# EDCPSU.net
KiCad netlist of a schematic drawn in EAGLE
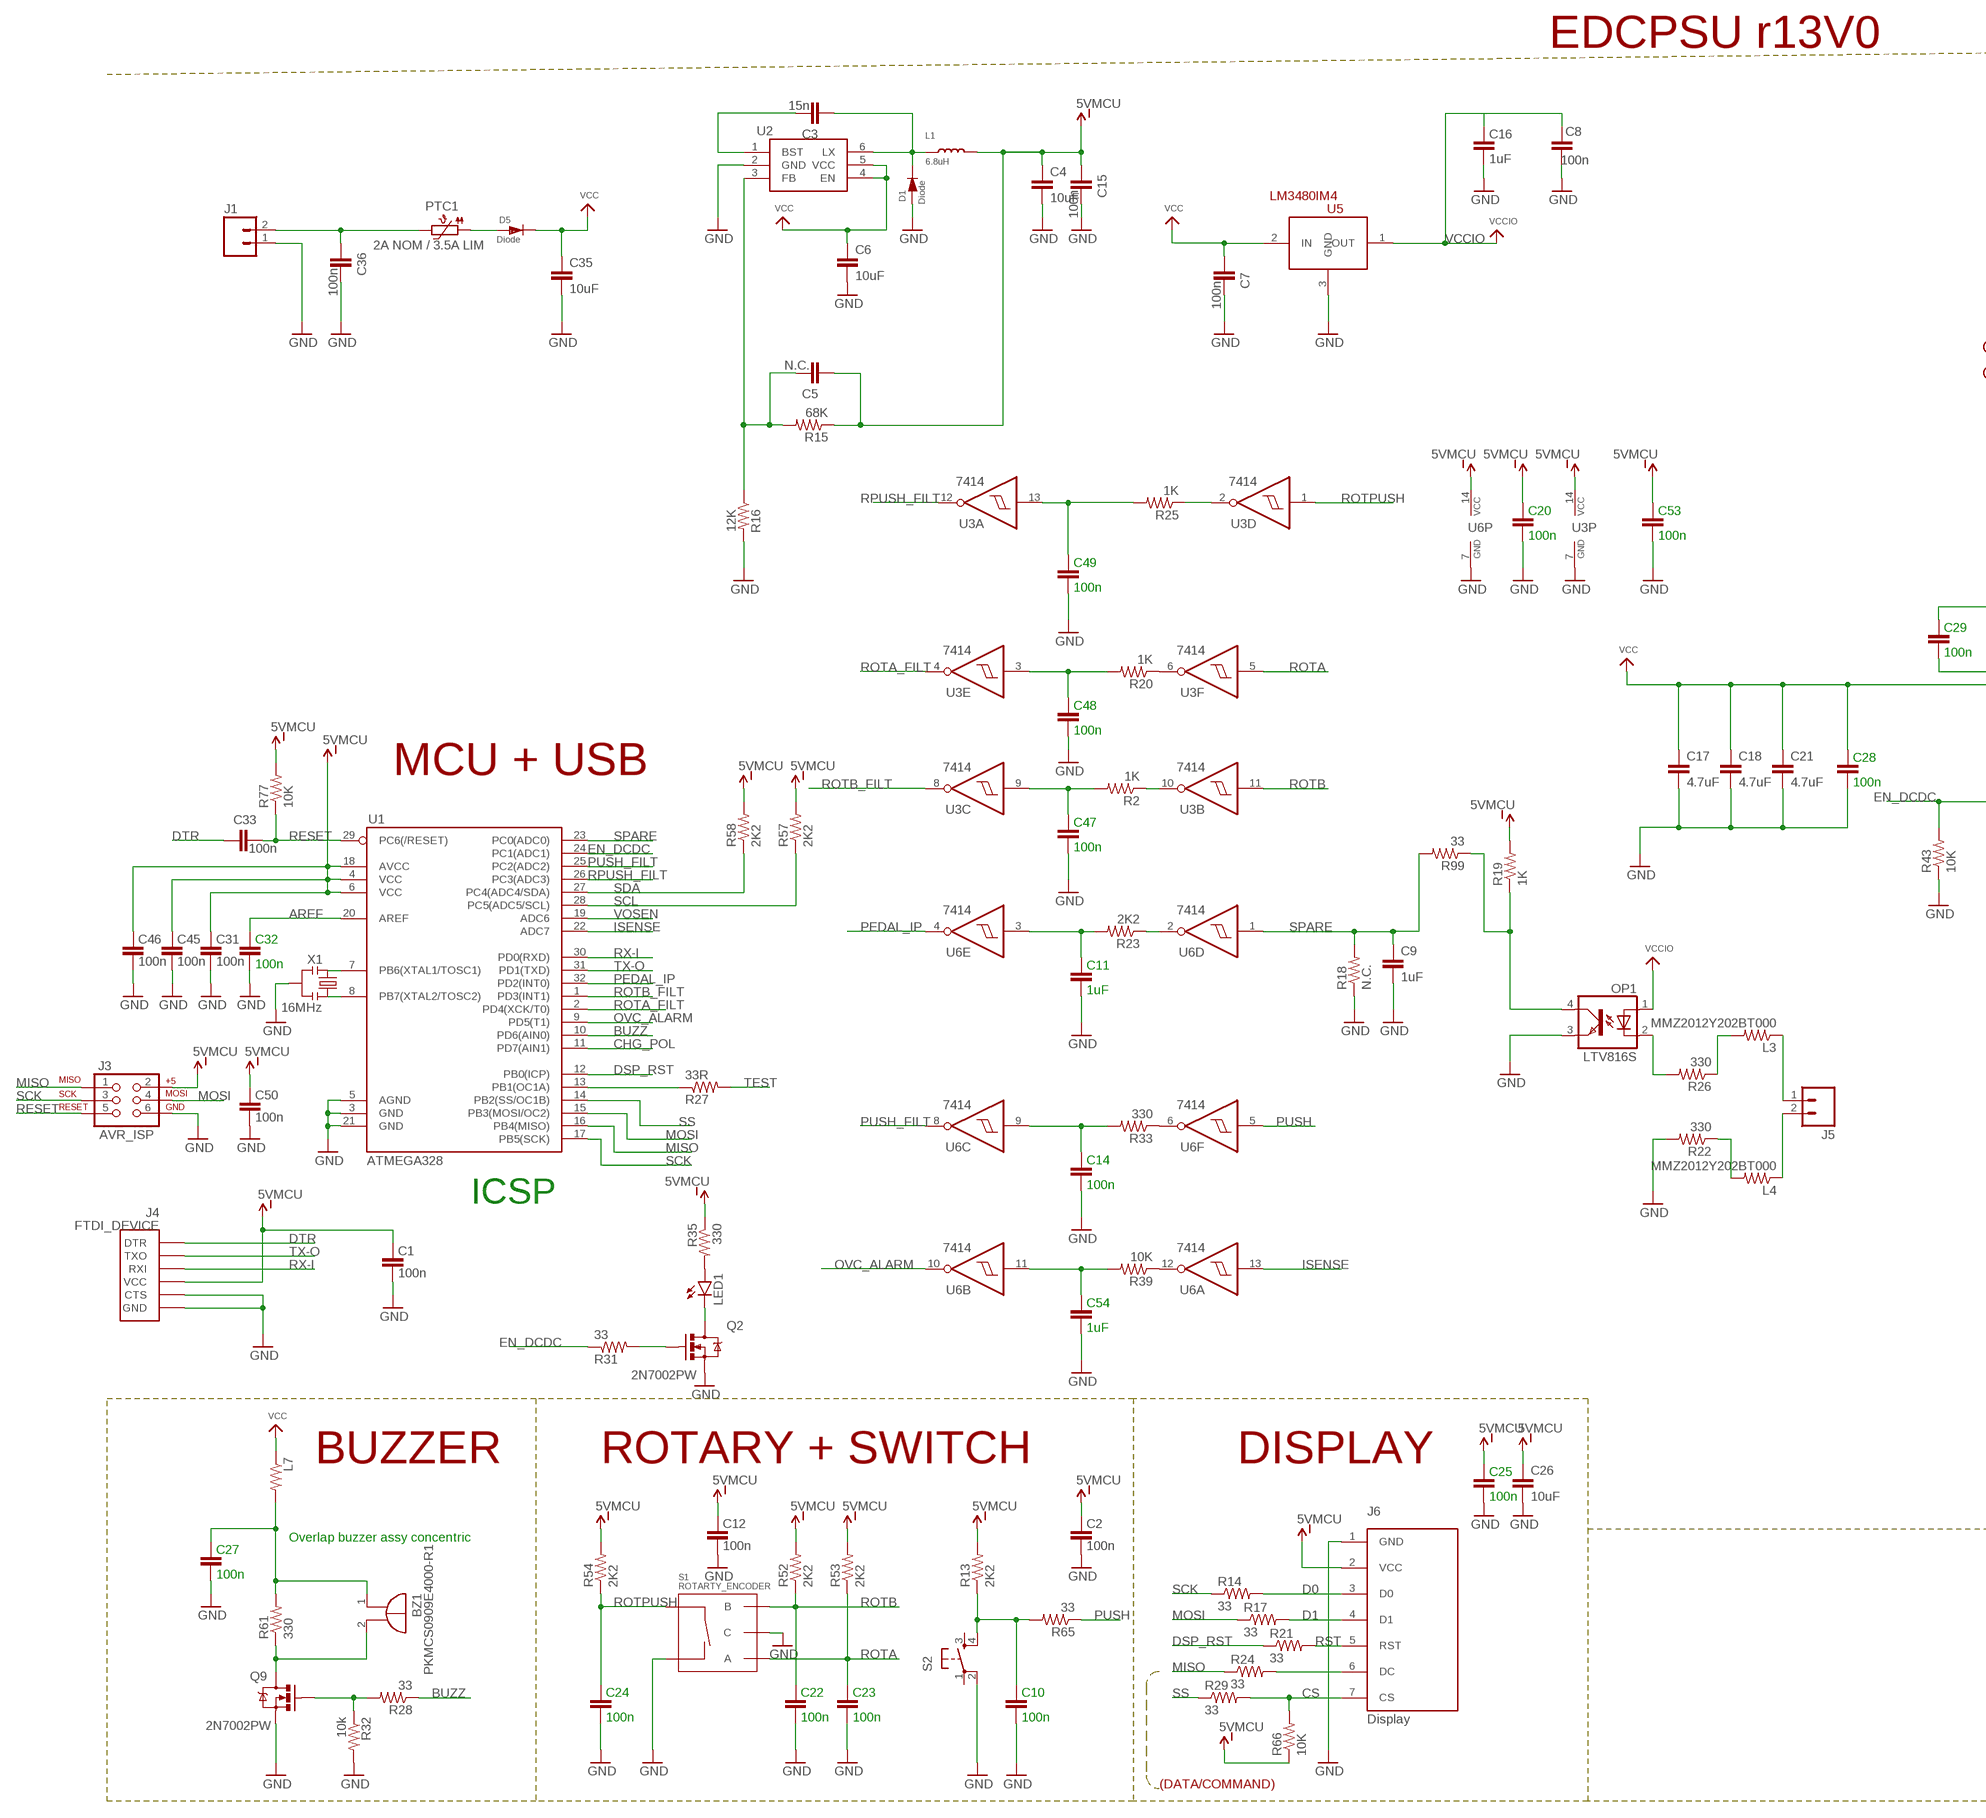
[diagram p0: schematic, sheet 1, part 1 of 2]
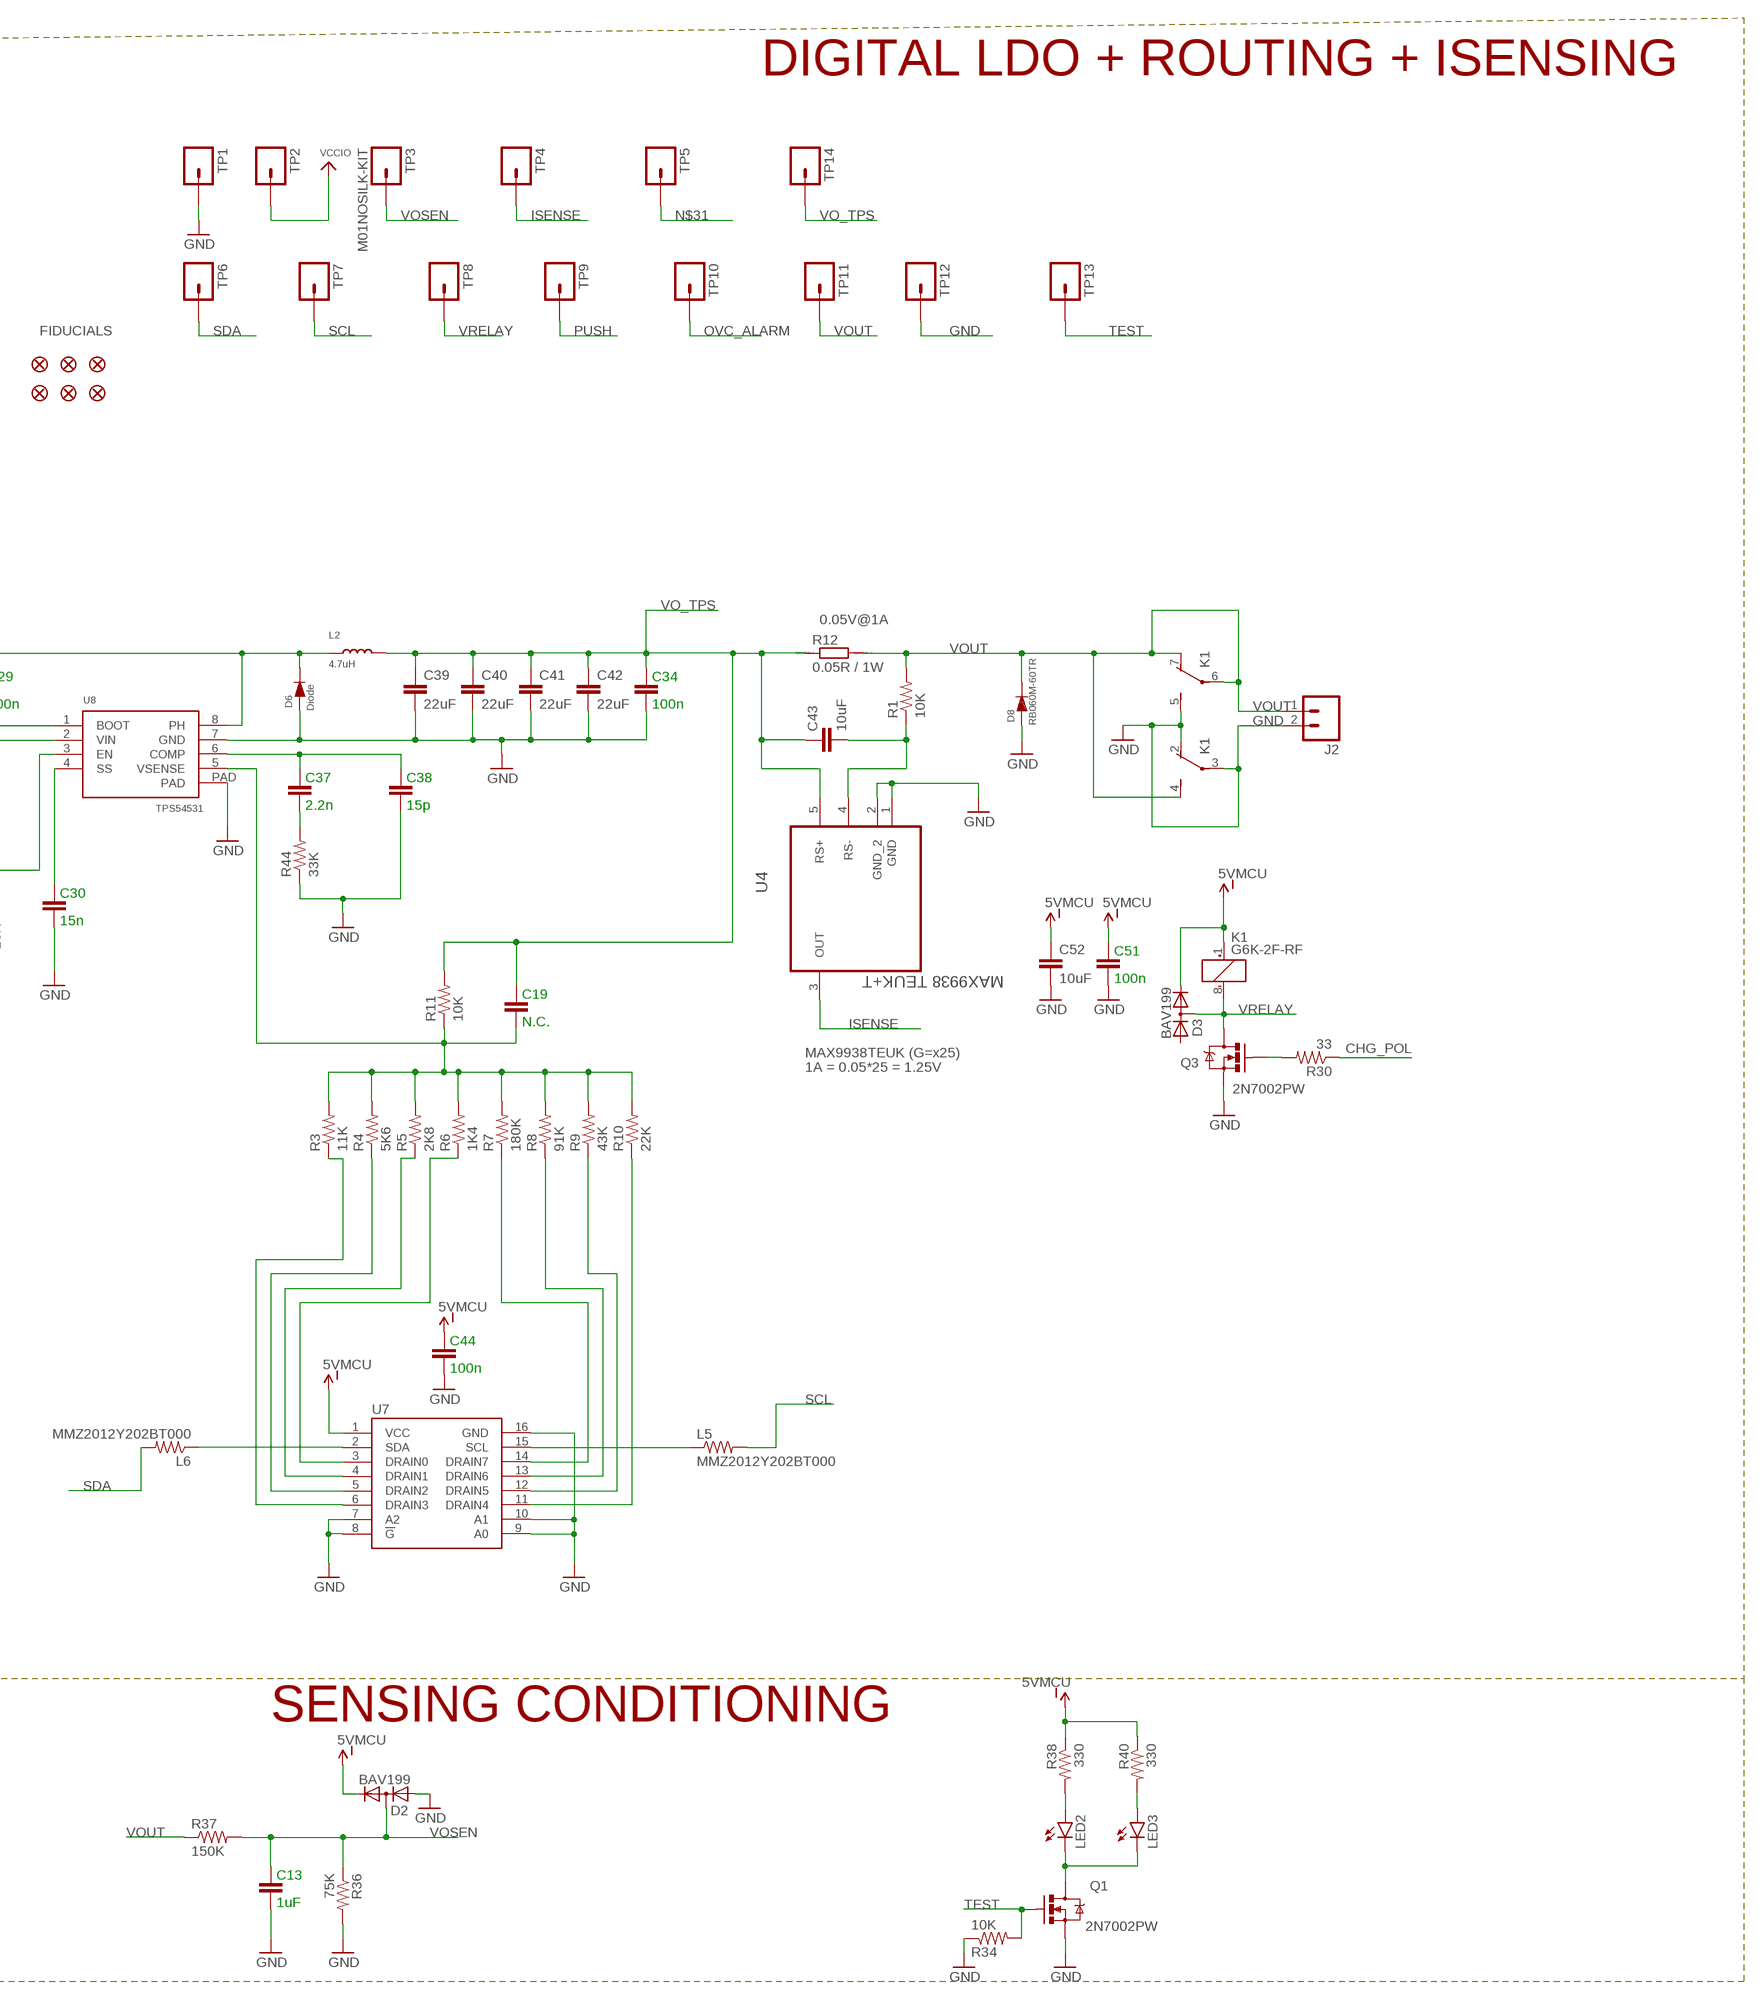
[diagram p1: schematic, sheet 1, part 2 of 2]

(export (version "E")
  (design (tool "Eeschema 10.0.6"))
  (components
    (comp (ref "BZ1")
      (value "PKMCS0909E4000-R1")
      (footprint "eagle-import:PKMCS0909")
      (libsource (lib "eagle-import") (part "PKMCS0909E4000-R1"))
    )
    (comp (ref "C1")
      (value "100n")
      (footprint "eagle-import:0805")
      (libsource (lib "eagle-import") (part "CAP0805"))
    )
    (comp (ref "C2")
      (value "100n")
      (footprint "eagle-import:0805")
      (libsource (lib "eagle-import") (part "CAP0805"))
    )
    (comp (ref "C3")
      (value "15n")
      (footprint "eagle-import:0805")
      (libsource (lib "eagle-import") (part "CAP0805"))
    )
    (comp (ref "C4")
      (value "10uF")
      (footprint "eagle-import:1206")
      (libsource (lib "eagle-import") (part "SparkFun-Passives_CAP1206"))
    )
    (comp (ref "C5")
      (value "N.C.")
      (footprint "eagle-import:0805")
      (libsource (lib "eagle-import") (part "CAP0805"))
    )
    (comp (ref "C6")
      (value "10uF")
      (footprint "eagle-import:1206")
      (libsource (lib "eagle-import") (part "SparkFun-Passives_CAP1206"))
    )
    (comp (ref "C7")
      (value "100n")
      (footprint "eagle-import:0805")
      (libsource (lib "eagle-import") (part "CAP0805"))
    )
    (comp (ref "C8")
      (value "100n")
      (footprint "eagle-import:0805")
      (libsource (lib "eagle-import") (part "CAP0805"))
    )
    (comp (ref "C9")
      (value "1uF")
      (footprint "eagle-import:1206")
      (libsource (lib "eagle-import") (part "SparkFun-Passives_CAP1206"))
    )
    (comp (ref "C10")
      (value "100n")
      (footprint "eagle-import:0805")
      (libsource (lib "eagle-import") (part "CAP0805"))
    )
    (comp (ref "C11")
      (value "1uF")
      (footprint "eagle-import:0805")
      (libsource (lib "eagle-import") (part "CAP0805"))
    )
    (comp (ref "C12")
      (value "100n")
      (footprint "eagle-import:0805")
      (libsource (lib "eagle-import") (part "CAP0805"))
    )
    (comp (ref "C13")
      (value "1uF")
      (footprint "eagle-import:0805")
      (libsource (lib "eagle-import") (part "CAP0805"))
    )
    (comp (ref "C14")
      (value "100n")
      (footprint "eagle-import:0805")
      (libsource (lib "eagle-import") (part "CAP0805"))
    )
    (comp (ref "C15")
      (value "100n")
      (footprint "eagle-import:0805")
      (libsource (lib "eagle-import") (part "CAP0805"))
    )
    (comp (ref "C16")
      (value "1uF")
      (footprint "eagle-import:0805")
      (libsource (lib "eagle-import") (part "CAP0805"))
    )
    (comp (ref "C17")
      (value "4.7uF")
      (footprint "eagle-import:1210")
      (libsource (lib "eagle-import") (part "SparkFun-Passives_CAP1210"))
    )
    (comp (ref "C18")
      (value "4.7uF")
      (footprint "eagle-import:1210")
      (libsource (lib "eagle-import") (part "SparkFun-Passives_CAP1210"))
    )
    (comp (ref "C19")
      (value "N.C.")
      (footprint "eagle-import:0805")
      (libsource (lib "eagle-import") (part "CAP0805"))
    )
    (comp (ref "C20")
      (value "100n")
      (footprint "eagle-import:0805")
      (libsource (lib "eagle-import") (part "CAP0805"))
    )
    (comp (ref "C21")
      (value "4.7uF")
      (footprint "eagle-import:1210")
      (libsource (lib "eagle-import") (part "SparkFun-Passives_CAP1210"))
    )
    (comp (ref "C22")
      (value "100n")
      (footprint "eagle-import:0805")
      (libsource (lib "eagle-import") (part "CAP0805"))
    )
    (comp (ref "C23")
      (value "100n")
      (footprint "eagle-import:0805")
      (libsource (lib "eagle-import") (part "CAP0805"))
    )
    (comp (ref "C24")
      (value "100n")
      (footprint "eagle-import:0805")
      (libsource (lib "eagle-import") (part "CAP0805"))
    )
    (comp (ref "C25")
      (value "100n")
      (footprint "eagle-import:0805")
      (libsource (lib "eagle-import") (part "CAP0805"))
    )
    (comp (ref "C26")
      (value "10uF")
      (footprint "eagle-import:1206")
      (libsource (lib "eagle-import") (part "SparkFun-Passives_CAP1206"))
    )
    (comp (ref "C27")
      (value "100n")
      (footprint "eagle-import:0805")
      (libsource (lib "eagle-import") (part "CAP0805"))
    )
    (comp (ref "C28")
      (value "100n")
      (footprint "eagle-import:0805")
      (libsource (lib "eagle-import") (part "CAP0805"))
    )
    (comp (ref "C29")
      (value "100n")
      (footprint "eagle-import:0805")
      (libsource (lib "eagle-import") (part "CAP0805"))
    )
    (comp (ref "C30")
      (value "15n")
      (footprint "eagle-import:0805")
      (libsource (lib "eagle-import") (part "CAP0805"))
    )
    (comp (ref "C31")
      (value "100n")
      (footprint "eagle-import:0805")
      (libsource (lib "eagle-import") (part "CAP0805"))
    )
    (comp (ref "C32")
      (value "100n")
      (footprint "eagle-import:0805")
      (libsource (lib "eagle-import") (part "CAP0805"))
    )
    (comp (ref "C33")
      (value "100n")
      (footprint "eagle-import:0805")
      (libsource (lib "eagle-import") (part "CAP0805"))
    )
    (comp (ref "C34")
      (value "100n")
      (footprint "eagle-import:0805")
      (libsource (lib "eagle-import") (part "CAP0805"))
    )
    (comp (ref "C35")
      (value "10uF")
      (footprint "eagle-import:1206")
      (libsource (lib "eagle-import") (part "SparkFun-Passives_CAP1206"))
    )
    (comp (ref "C36")
      (value "100n")
      (footprint "eagle-import:0805")
      (libsource (lib "eagle-import") (part "CAP0805"))
    )
    (comp (ref "C37")
      (value "2.2n")
      (footprint "eagle-import:0805")
      (libsource (lib "eagle-import") (part "CAP0805"))
    )
    (comp (ref "C38")
      (value "15p")
      (footprint "eagle-import:0805")
      (libsource (lib "eagle-import") (part "CAP0805"))
    )
    (comp (ref "C39")
      (value "22uF")
      (footprint "eagle-import:1210")
      (libsource (lib "eagle-import") (part "SparkFun-Passives_CAP1210"))
    )
    (comp (ref "C40")
      (value "22uF")
      (footprint "eagle-import:1210")
      (libsource (lib "eagle-import") (part "SparkFun-Passives_CAP1210"))
    )
    (comp (ref "C41")
      (value "22uF")
      (footprint "eagle-import:1210")
      (libsource (lib "eagle-import") (part "SparkFun-Passives_CAP1210"))
    )
    (comp (ref "C42")
      (value "22uF")
      (footprint "eagle-import:1210")
      (libsource (lib "eagle-import") (part "SparkFun-Passives_CAP1210"))
    )
    (comp (ref "C43")
      (value "10uF")
      (footprint "eagle-import:1206")
      (libsource (lib "eagle-import") (part "SparkFun-Passives_CAP1206"))
    )
    (comp (ref "C44")
      (value "100n")
      (footprint "eagle-import:0805")
      (libsource (lib "eagle-import") (part "CAP0805"))
    )
    (comp (ref "C45")
      (value "100n")
      (footprint "eagle-import:0805")
      (libsource (lib "eagle-import") (part "CAP0805"))
    )
    (comp (ref "C46")
      (value "100n")
      (footprint "eagle-import:0805")
      (libsource (lib "eagle-import") (part "CAP0805"))
    )
    (comp (ref "C47")
      (value "100n")
      (footprint "eagle-import:0805")
      (libsource (lib "eagle-import") (part "CAP0805"))
    )
    (comp (ref "C48")
      (value "100n")
      (footprint "eagle-import:0805")
      (libsource (lib "eagle-import") (part "CAP0805"))
    )
    (comp (ref "C49")
      (value "100n")
      (footprint "eagle-import:0805")
      (libsource (lib "eagle-import") (part "CAP0805"))
    )
    (comp (ref "C50")
      (value "100n")
      (footprint "eagle-import:0805")
      (libsource (lib "eagle-import") (part "CAP0805"))
    )
    (comp (ref "C51")
      (value "100n")
      (footprint "eagle-import:0805")
      (libsource (lib "eagle-import") (part "CAP0805"))
    )
    (comp (ref "C52")
      (value "10uF")
      (footprint "eagle-import:1206")
      (libsource (lib "eagle-import") (part "SparkFun-Passives_CAP1206"))
    )
    (comp (ref "C53")
      (value "100n")
      (footprint "eagle-import:0805")
      (libsource (lib "eagle-import") (part "CAP0805"))
    )
    (comp (ref "C54")
      (value "1uF")
      (footprint "eagle-import:0805")
      (libsource (lib "eagle-import") (part "CAP0805"))
    )
    (comp (ref "D1")
      (value "Diode")
      (footprint "eagle-import:SOD123")
      (libsource (lib "eagle-import") (part "DSOD123"))
    )
    (comp (ref "D2")
      (value "BAV199")
      (footprint "eagle-import:SOT23")
      (libsource (lib "eagle-import") (part "BAV199"))
    )
    (comp (ref "D3")
      (value "BAV199")
      (footprint "eagle-import:SOT23")
      (libsource (lib "eagle-import") (part "BAV199"))
    )
    (comp (ref "D5")
      (value "Diode")
      (footprint "eagle-import:DO-214AB")
      (libsource (lib "eagle-import") (part "DSMC"))
    )
    (comp (ref "D6")
      (value "Diode")
      (footprint "eagle-import:DO-214AB")
      (libsource (lib "eagle-import") (part "DSMC"))
    )
    (comp (ref "D8")
      (value "RB060M-60TR")
      (footprint "eagle-import:SMADIODE")
      (libsource (lib "eagle-import") (part "DSMA"))
    )
    (comp (ref "FID1")
      (value "FIDUCIAL1X2")
      (footprint "eagle-import:FIDUCIAL-1X2")
      (libsource (lib "eagle-import") (part "FIDUCIAL1X2"))
    )
    (comp (ref "FID2")
      (value "FIDUCIAL1X2")
      (footprint "eagle-import:FIDUCIAL-1X2")
      (libsource (lib "eagle-import") (part "FIDUCIAL1X2"))
    )
    (comp (ref "FID3")
      (value "FIDUCIAL1X2")
      (footprint "eagle-import:FIDUCIAL-1X2")
      (libsource (lib "eagle-import") (part "FIDUCIAL1X2"))
    )
    (comp (ref "FID4")
      (value "FIDUCIAL1X2")
      (footprint "eagle-import:FIDUCIAL-1X2")
      (libsource (lib "eagle-import") (part "FIDUCIAL1X2"))
    )
    (comp (ref "FID5")
      (value "FIDUCIAL1X2")
      (footprint "eagle-import:FIDUCIAL-1X2")
      (libsource (lib "eagle-import") (part "FIDUCIAL1X2"))
    )
    (comp (ref "FID6")
      (value "FIDUCIAL1X2")
      (footprint "eagle-import:FIDUCIAL-1X2")
      (libsource (lib "eagle-import") (part "FIDUCIAL1X2"))
    )
    (comp (ref "J1")
      (value "M02LOCK_LONGPADS")
      (footprint "eagle-import:1X02_LOCK_LONGPADS")
      (libsource (lib "eagle-import") (part "M02LOCK_LONGPADS"))
    )
    (comp (ref "J2")
      (value "M02LOCK_LONGPADS")
      (footprint "eagle-import:1X02_LOCK_LONGPADS")
      (libsource (lib "eagle-import") (part "M02LOCK_LONGPADS"))
    )
    (comp (ref "J3")
      (value "AVR_ISP")
      (footprint "eagle-import:2X3")
      (libsource (lib "eagle-import") (part "AVR_SPI_PRG_6PTH"))
    )
    (comp (ref "J4")
      (value "FTDI_DEVICE")
      (footprint "eagle-import:FTDI_DEVICE_SIDE")
      (libsource (lib "eagle-import") (part "FTDI_DEVICE"))
    )
    (comp (ref "J5")
      (value "M02LOCK_LONGPADS")
      (footprint "eagle-import:1X02_LOCK_LONGPADS")
      (libsource (lib "eagle-import") (part "M02LOCK_LONGPADS"))
    )
    (comp (ref "J6")
      (value "Display")
      (footprint "eagle-import:OLED_LCD")
      (libsource (lib "eagle-import") (part "OLED_LCD"))
    )
    (comp (ref "K1")
      (value "G6K-2F-RF")
      (footprint "eagle-import:G6K-RF")
      (fields (field (name "MF") "OMRON COMPONENTS USA") (field (name "MPN") "G6K-2F-RF-DC12"))
      (libsource (lib "eagle-import") (part "G6K-2F-RF"))
    )
    (comp (ref "L1")
      (value "6.8uH")
      (footprint "eagle-import:NR4018T100M")
      (libsource (lib "eagle-import") (part "L4018"))
    )
    (comp (ref "L2")
      (value "4.7uH")
      (footprint "eagle-import:WE-LHMI")
      (libsource (lib "eagle-import") (part "L74437368047"))
    )
    (comp (ref "L3")
      (value "MMZ2012Y202BT000")
      (footprint "eagle-import:0805")
      (libsource (lib "eagle-import") (part "RESISTOR0805-RES"))
    )
    (comp (ref "L4")
      (value "MMZ2012Y202BT000")
      (footprint "eagle-import:0805")
      (libsource (lib "eagle-import") (part "RESISTOR0805-RES"))
    )
    (comp (ref "L5")
      (value "MMZ2012Y202BT000")
      (footprint "eagle-import:0805")
      (libsource (lib "eagle-import") (part "RESISTOR0805-RES"))
    )
    (comp (ref "L6")
      (value "MMZ2012Y202BT000")
      (footprint "eagle-import:0805")
      (libsource (lib "eagle-import") (part "RESISTOR0805-RES"))
    )
    (comp (ref "L7")
      (value "MMZ2012Y202BT000")
      (footprint "eagle-import:0805")
      (libsource (lib "eagle-import") (part "RESISTOR0805-RES"))
    )
    (comp (ref "LED1")
      (value "LED3MM")
      (footprint "eagle-import:LED3MM")
      (libsource (lib "eagle-import") (part "LED3MM"))
    )
    (comp (ref "LED2")
      (value "LED5MM")
      (footprint "eagle-import:LED5MM")
      (libsource (lib "eagle-import") (part "LED5MM"))
    )
    (comp (ref "LED3")
      (value "LED5MM")
      (footprint "eagle-import:LED5MM")
      (libsource (lib "eagle-import") (part "LED5MM"))
    )
    (comp (ref "OP1")
      (value "LTV816S")
      (footprint "eagle-import:SMD4")
      (libsource (lib "eagle-import") (part "LTV816S"))
    )
    (comp (ref "PTC1")
      (value "2A NOM / 3.5A LIM")
      (footprint "eagle-import:1812L")
      (libsource (lib "eagle-import") (part "PTC-"))
    )
    (comp (ref "Q1")
      (value "2N7002PW")
      (footprint "eagle-import:SOT323")
      (libsource (lib "eagle-import") (part "MOSFET-NCHANNEL2N7002PW"))
    )
    (comp (ref "Q2")
      (value "2N7002PW")
      (footprint "eagle-import:SOT323")
      (libsource (lib "eagle-import") (part "MOSFET-NCHANNEL2N7002PW"))
    )
    (comp (ref "Q3")
      (value "2N7002PW")
      (footprint "eagle-import:SOT323")
      (libsource (lib "eagle-import") (part "MOSFET-NCHANNEL2N7002PW"))
    )
    (comp (ref "Q9")
      (value "2N7002PW")
      (footprint "eagle-import:SOT323")
      (libsource (lib "eagle-import") (part "MOSFET-NCHANNEL2N7002PW"))
    )
    (comp (ref "R1")
      (value "10K")
      (footprint "eagle-import:0805")
      (libsource (lib "eagle-import") (part "RESISTOR0805-RES"))
    )
    (comp (ref "R2")
      (value "1K")
      (footprint "eagle-import:0805")
      (libsource (lib "eagle-import") (part "RESISTOR0805-RES"))
    )
    (comp (ref "R3")
      (value "11K")
      (footprint "eagle-import:0805")
      (libsource (lib "eagle-import") (part "RESISTOR0805-RES"))
    )
    (comp (ref "R4")
      (value "5K6")
      (footprint "eagle-import:0805")
      (libsource (lib "eagle-import") (part "RESISTOR0805-RES"))
    )
    (comp (ref "R5")
      (value "2K8")
      (footprint "eagle-import:0805")
      (libsource (lib "eagle-import") (part "RESISTOR0805-RES"))
    )
    (comp (ref "R6")
      (value "1K4")
      (footprint "eagle-import:0805")
      (libsource (lib "eagle-import") (part "RESISTOR0805-RES"))
    )
    (comp (ref "R7")
      (value "180K")
      (footprint "eagle-import:0805")
      (libsource (lib "eagle-import") (part "RESISTOR0805-RES"))
    )
    (comp (ref "R8")
      (value "91K")
      (footprint "eagle-import:0805")
      (libsource (lib "eagle-import") (part "RESISTOR0805-RES"))
    )
    (comp (ref "R9")
      (value "43K")
      (footprint "eagle-import:0805")
      (libsource (lib "eagle-import") (part "RESISTOR0805-RES"))
    )
    (comp (ref "R10")
      (value "22K")
      (footprint "eagle-import:0805")
      (libsource (lib "eagle-import") (part "RESISTOR0805-RES"))
    )
    (comp (ref "R11")
      (value "10K")
      (footprint "eagle-import:0805")
      (libsource (lib "eagle-import") (part "RESISTOR0805-RES"))
    )
    (comp (ref "R12")
      (value "0.05R / 1W")
      (footprint "eagle-import:R2512")
      (libsource (lib "eagle-import") (part "RR2512"))
    )
    (comp (ref "R13")
      (value "2K2")
      (footprint "eagle-import:0805")
      (libsource (lib "eagle-import") (part "RESISTOR0805-RES"))
    )
    (comp (ref "R14")
      (value "33")
      (footprint "eagle-import:0805")
      (libsource (lib "eagle-import") (part "RESISTOR0805-RES"))
    )
    (comp (ref "R15")
      (value "68K")
      (footprint "eagle-import:0805")
      (libsource (lib "eagle-import") (part "RESISTOR0805-RES"))
    )
    (comp (ref "R16")
      (value "12K")
      (footprint "eagle-import:0805")
      (libsource (lib "eagle-import") (part "RESISTOR0805-RES"))
    )
    (comp (ref "R17")
      (value "33")
      (footprint "eagle-import:0805")
      (libsource (lib "eagle-import") (part "RESISTOR0805-RES"))
    )
    (comp (ref "R18")
      (value "N.C.")
      (footprint "eagle-import:0805")
      (libsource (lib "eagle-import") (part "RESISTOR0805-RES"))
    )
    (comp (ref "R19")
      (value "1K")
      (footprint "eagle-import:0805")
      (libsource (lib "eagle-import") (part "RESISTOR0805-RES"))
    )
    (comp (ref "R20")
      (value "1K")
      (footprint "eagle-import:0805")
      (libsource (lib "eagle-import") (part "RESISTOR0805-RES"))
    )
    (comp (ref "R21")
      (value "33")
      (footprint "eagle-import:0805")
      (libsource (lib "eagle-import") (part "RESISTOR0805-RES"))
    )
    (comp (ref "R22")
      (value "330")
      (footprint "eagle-import:1206")
      (libsource (lib "eagle-import") (part "SparkFun-Passives_RESISTOR1206"))
    )
    (comp (ref "R23")
      (value "2K2")
      (footprint "eagle-import:0805")
      (libsource (lib "eagle-import") (part "RESISTOR0805-RES"))
    )
    (comp (ref "R24")
      (value "33")
      (footprint "eagle-import:0805")
      (libsource (lib "eagle-import") (part "RESISTOR0805-RES"))
    )
    (comp (ref "R25")
      (value "1K")
      (footprint "eagle-import:0805")
      (libsource (lib "eagle-import") (part "RESISTOR0805-RES"))
    )
    (comp (ref "R26")
      (value "330")
      (footprint "eagle-import:1206")
      (libsource (lib "eagle-import") (part "SparkFun-Passives_RESISTOR1206"))
    )
    (comp (ref "R27")
      (value "33R")
      (footprint "eagle-import:0805")
      (libsource (lib "eagle-import") (part "RESISTOR0805-RES"))
    )
    (comp (ref "R28")
      (value "33")
      (footprint "eagle-import:0805")
      (libsource (lib "eagle-import") (part "RESISTOR0805-RES"))
    )
    (comp (ref "R29")
      (value "33")
      (footprint "eagle-import:0805")
      (libsource (lib "eagle-import") (part "RESISTOR0805-RES"))
    )
    (comp (ref "R30")
      (value "33")
      (footprint "eagle-import:0805")
      (libsource (lib "eagle-import") (part "RESISTOR0805-RES"))
    )
    (comp (ref "R31")
      (value "33")
      (footprint "eagle-import:0805")
      (libsource (lib "eagle-import") (part "RESISTOR0805-RES"))
    )
    (comp (ref "R32")
      (value "10k")
      (footprint "eagle-import:0805")
      (libsource (lib "eagle-import") (part "RESISTOR0805-RES"))
    )
    (comp (ref "R33")
      (value "330")
      (footprint "eagle-import:0805")
      (libsource (lib "eagle-import") (part "RESISTOR0805-RES"))
    )
    (comp (ref "R34")
      (value "10K")
      (footprint "eagle-import:0805")
      (libsource (lib "eagle-import") (part "RESISTOR0805-RES"))
    )
    (comp (ref "R35")
      (value "330")
      (footprint "eagle-import:0805")
      (libsource (lib "eagle-import") (part "RESISTOR0805-RES"))
    )
    (comp (ref "R36")
      (value "75K")
      (footprint "eagle-import:0805")
      (libsource (lib "eagle-import") (part "RESISTOR0805-RES"))
    )
    (comp (ref "R37")
      (value "150K")
      (footprint "eagle-import:0805")
      (libsource (lib "eagle-import") (part "RESISTOR0805-RES"))
    )
    (comp (ref "R38")
      (value "330")
      (footprint "eagle-import:0805")
      (libsource (lib "eagle-import") (part "RESISTOR0805-RES"))
    )
    (comp (ref "R39")
      (value "10K")
      (footprint "eagle-import:0805")
      (libsource (lib "eagle-import") (part "RESISTOR0805-RES"))
    )
    (comp (ref "R40")
      (value "330")
      (footprint "eagle-import:0805")
      (libsource (lib "eagle-import") (part "RESISTOR0805-RES"))
    )
    (comp (ref "R43")
      (value "10K")
      (footprint "eagle-import:0805")
      (libsource (lib "eagle-import") (part "RESISTOR0805-RES"))
    )
    (comp (ref "R44")
      (value "33K")
      (footprint "eagle-import:0805")
      (libsource (lib "eagle-import") (part "RESISTOR0805-RES"))
    )
    (comp (ref "R52")
      (value "2K2")
      (footprint "eagle-import:0805")
      (libsource (lib "eagle-import") (part "RESISTOR0805-RES"))
    )
    (comp (ref "R53")
      (value "2K2")
      (footprint "eagle-import:0805")
      (libsource (lib "eagle-import") (part "RESISTOR0805-RES"))
    )
    (comp (ref "R54")
      (value "2K2")
      (footprint "eagle-import:0805")
      (libsource (lib "eagle-import") (part "RESISTOR0805-RES"))
    )
    (comp (ref "R57")
      (value "2K2")
      (footprint "eagle-import:0805")
      (libsource (lib "eagle-import") (part "RESISTOR0805-RES"))
    )
    (comp (ref "R58")
      (value "2K2")
      (footprint "eagle-import:0805")
      (libsource (lib "eagle-import") (part "RESISTOR0805-RES"))
    )
    (comp (ref "R61")
      (value "330")
      (footprint "eagle-import:0805")
      (libsource (lib "eagle-import") (part "RESISTOR0805-RES"))
    )
    (comp (ref "R65")
      (value "33")
      (footprint "eagle-import:0805")
      (libsource (lib "eagle-import") (part "RESISTOR0805-RES"))
    )
    (comp (ref "R66")
      (value "10K")
      (footprint "eagle-import:0805")
      (libsource (lib "eagle-import") (part "RESISTOR0805-RES"))
    )
    (comp (ref "R77")
      (value "10K")
      (footprint "eagle-import:0805")
      (libsource (lib "eagle-import") (part "RESISTOR0805-RES"))
    )
    (comp (ref "R99")
      (value "33")
      (footprint "eagle-import:0805")
      (libsource (lib "eagle-import") (part "RESISTOR0805-RES"))
    )
    (comp (ref "S1")
      (value "ROTARTY_ENCODER")
      (footprint "eagle-import:ROTARY_ENC_PLAIN")
      (libsource (lib "eagle-import") (part "ROTARTY_ENCODER"))
    )
    (comp (ref "S2")
      (value "TAC_SWITCH_KSC931G-SMD")
      (footprint "eagle-import:TAC_SW_SMD_KSC931G")
      (libsource (lib "eagle-import") (part "TAC_SWITCH_KSC931G-SMD"))
    )
    (comp (ref "TP1")
      (value "M01POGOPIN_HOLE_LARGE")
      (footprint "eagle-import:1X01_POGOPIN_HOLE_LARGE")
      (libsource (lib "eagle-import") (part "M01POGOPIN_HOLE_LARGE"))
    )
    (comp (ref "TP2")
      (value "M01POGOPIN_HOLE_LARGE")
      (footprint "eagle-import:1X01_POGOPIN_HOLE_LARGE")
      (libsource (lib "eagle-import") (part "M01POGOPIN_HOLE_LARGE"))
    )
    (comp (ref "TP3")
      (value "M01NOSILK-KIT")
      (footprint "eagle-import:1X01NS-KIT")
      (libsource (lib "eagle-import") (part "M01NOSILK-KIT"))
    )
    (comp (ref "TP4")
      (value "M01POGOPIN_HOLE_LARGE")
      (footprint "eagle-import:1X01_POGOPIN_HOLE_LARGE")
      (libsource (lib "eagle-import") (part "M01POGOPIN_HOLE_LARGE"))
    )
    (comp (ref "TP5")
      (value "M01POGOPIN_HOLE_LARGE")
      (footprint "eagle-import:1X01_POGOPIN_HOLE_LARGE")
      (libsource (lib "eagle-import") (part "M01POGOPIN_HOLE_LARGE"))
    )
    (comp (ref "TP6")
      (value "M01POGOPIN_HOLE_LARGE")
      (footprint "eagle-import:1X01_POGOPIN_HOLE_LARGE")
      (libsource (lib "eagle-import") (part "M01POGOPIN_HOLE_LARGE"))
    )
    (comp (ref "TP7")
      (value "M01POGOPIN_HOLE_LARGE")
      (footprint "eagle-import:1X01_POGOPIN_HOLE_LARGE")
      (libsource (lib "eagle-import") (part "M01POGOPIN_HOLE_LARGE"))
    )
    (comp (ref "TP8")
      (value "M01POGOPIN_HOLE_LARGE")
      (footprint "eagle-import:1X01_POGOPIN_HOLE_LARGE")
      (libsource (lib "eagle-import") (part "M01POGOPIN_HOLE_LARGE"))
    )
    (comp (ref "TP9")
      (value "M01POGOPIN_HOLE_LARGE")
      (footprint "eagle-import:1X01_POGOPIN_HOLE_LARGE")
      (libsource (lib "eagle-import") (part "M01POGOPIN_HOLE_LARGE"))
    )
    (comp (ref "TP10")
      (value "M01POGOPIN_HOLE_LARGE")
      (footprint "eagle-import:1X01_POGOPIN_HOLE_LARGE")
      (libsource (lib "eagle-import") (part "M01POGOPIN_HOLE_LARGE"))
    )
    (comp (ref "TP11")
      (value "M01POGOPIN_HOLE_LARGE")
      (footprint "eagle-import:1X01_POGOPIN_HOLE_LARGE")
      (libsource (lib "eagle-import") (part "M01POGOPIN_HOLE_LARGE"))
    )
    (comp (ref "TP12")
      (value "M01POGOPIN_HOLE_LARGE")
      (footprint "eagle-import:1X01_POGOPIN_HOLE_LARGE")
      (libsource (lib "eagle-import") (part "M01POGOPIN_HOLE_LARGE"))
    )
    (comp (ref "TP13")
      (value "M01POGOPIN_HOLE_LARGE")
      (footprint "eagle-import:1X01_POGOPIN_HOLE_LARGE")
      (libsource (lib "eagle-import") (part "M01POGOPIN_HOLE_LARGE"))
    )
    (comp (ref "TP14")
      (value "M01POGOPIN_HOLE_LARGE")
      (footprint "eagle-import:1X01_POGOPIN_HOLE_LARGE")
      (libsource (lib "eagle-import") (part "M01POGOPIN_HOLE_LARGE"))
    )
    (comp (ref "U1")
      (value "ATMEGA328")
      (footprint "eagle-import:TQFP32-08")
      (libsource (lib "eagle-import") (part "ATMEGA168"))
    )
    (comp (ref "U2")
      (value "BD9G101G")
      (footprint "eagle-import:SSOP6")
      (libsource (lib "eagle-import") (part "BD9G101G"))
    )
    (comp (ref "U3")
      (value "7414")
      (footprint "eagle-import:TSSOP14")
      (libsource (lib "eagle-import") (part "7414"))
    )
    (comp (ref "U4")
      (value "MAX9938 TEUK+T")
      (footprint "eagle-import:SOT95P280X145-5N")
      (fields (field (name "MPN") "MAX9938FEUK+T"))
      (libsource (lib "eagle-import") (part "MAX9938FEUK+T"))
    )
    (comp (ref "U5")
      (value "LM3480IM4")
      (footprint "eagle-import:SOT23-3")
      (libsource (lib "eagle-import") (part "LM3480IM4"))
    )
    (comp (ref "U6")
      (value "7414")
      (footprint "eagle-import:TSSOP14")
      (libsource (lib "eagle-import") (part "7414"))
    )
    (comp (ref "U7")
      (value "TPIC2810D")
      (footprint "eagle-import:SO16")
      (libsource (lib "eagle-import") (part "TPIC2810D"))
    )
    (comp (ref "U8")
      (value "TPS54531")
      (footprint "eagle-import:SOIC8")
      (libsource (lib "eagle-import") (part "TPS5431DDAR"))
    )
    (comp (ref "X1")
      (value "16MHz")
      (footprint "eagle-import:RESONATOR-SMD")
      (libsource (lib "eagle-import") (part "RESONATORSMD"))
    )
  )
  (nets
    (net (code "1") (name "/AREF") (class "Default")
      (node (ref "C32") (pin "2") (pinfunction "2_2") (pintype "passive"))
      (node (ref "U1") (pin "20") (pinfunction "AREF_20") (pintype "bidirectional"))
    )
    (net (code "2") (name "/BUZZ") (class "Default")
      (node (ref "R28") (pin "1") (pinfunction "1_1") (pintype "passive"))
      (node (ref "U1") (pin "10") (pinfunction "PD6(AIN0)_10") (pintype "bidirectional"))
    )
    (net (code "3") (name "/CHG_POL") (class "Default")
      (node (ref "R30") (pin "1") (pinfunction "1_1") (pintype "passive"))
      (node (ref "U1") (pin "11") (pinfunction "PD7(AIN1)_11") (pintype "bidirectional"))
    )
    (net (code "4") (name "/CS") (class "Default")
      (node (ref "J6") (pin "7") (pinfunction "CS_7") (pintype "bidirectional"))
      (node (ref "R29") (pin "2") (pinfunction "2_2") (pintype "passive"))
      (node (ref "R66") (pin "2") (pinfunction "2_2") (pintype "passive"))
    )
    (net (code "5") (name "/D0") (class "Default")
      (node (ref "J6") (pin "3") (pinfunction "D0_3") (pintype "bidirectional"))
      (node (ref "R14") (pin "2") (pinfunction "2_2") (pintype "passive"))
    )
    (net (code "6") (name "/D1") (class "Default")
      (node (ref "J6") (pin "4") (pinfunction "D1_4") (pintype "bidirectional"))
      (node (ref "R17") (pin "2") (pinfunction "2_2") (pintype "passive"))
    )
    (net (code "7") (name "/DSP_RST") (class "Default")
      (node (ref "R21") (pin "1") (pinfunction "1_1") (pintype "passive"))
      (node (ref "U1") (pin "12") (pinfunction "PB0(ICP)_12") (pintype "bidirectional"))
    )
    (net (code "8") (name "/DTR") (class "Default")
      (node (ref "C33") (pin "2") (pinfunction "2_2") (pintype "passive"))
      (node (ref "J4") (pin "P$1") (pinfunction "DTR_P$1") (pintype "bidirectional"))
    )
    (net (code "9") (name "/EN_DCDC") (class "Default")
      (node (ref "R31") (pin "1") (pinfunction "1_1") (pintype "passive"))
      (node (ref "R43") (pin "2") (pinfunction "2_2") (pintype "passive"))
      (node (ref "U1") (pin "24") (pinfunction "PC1(ADC1)_24") (pintype "bidirectional"))
      (node (ref "U8") (pin "3") (pinfunction "EN_3") (pintype "bidirectional"))
    )
    (net (code "10") (name "/ISENSE") (class "Default")
      (node (ref "TP4") (pin "1") (pinfunction "1_1") (pintype "passive"))
      (node (ref "U1") (pin "22") (pinfunction "ADC7_22") (pintype "bidirectional"))
      (node (ref "U4") (pin "3") (pinfunction "OUT_3") (pintype "output"))
      (node (ref "U6") (pin "13") (pinfunction "I_13") (pintype "input"))
    )
    (net (code "11") (name "/MISO") (class "Default")
      (node (ref "J3") (pin "1") (pinfunction "1_1") (pintype "passive"))
      (node (ref "R24") (pin "1") (pinfunction "1_1") (pintype "passive"))
      (node (ref "U1") (pin "16") (pinfunction "PB4(MISO)_16") (pintype "bidirectional"))
    )
    (net (code "12") (name "/MOSI") (class "Default")
      (node (ref "J3") (pin "4") (pinfunction "4_4") (pintype "passive"))
      (node (ref "R17") (pin "1") (pinfunction "1_1") (pintype "passive"))
      (node (ref "U1") (pin "15") (pinfunction "PB3(MOSI/OC2)_15") (pintype "bidirectional"))
    )
    (net (code "13") (name "/N$31") (class "Default")
      (node (ref "OP1") (pin "4") (pinfunction "COL_4") (pintype "passive"))
      (node (ref "R19") (pin "1") (pinfunction "1_1") (pintype "passive"))
      (node (ref "R99") (pin "1") (pinfunction "1_1") (pintype "passive"))
      (node (ref "TP5") (pin "1") (pinfunction "1_1") (pintype "passive"))
    )
    (net (code "14") (name "/OVC_ALARM") (class "Default")
      (node (ref "TP10") (pin "1") (pinfunction "1_1") (pintype "passive"))
      (node (ref "U1") (pin "9") (pinfunction "PD5(T1)_9") (pintype "bidirectional"))
      (node (ref "U6") (pin "10") (pinfunction "O_10") (pintype "output"))
    )
    (net (code "15") (name "/PEDAL_IP") (class "Default")
      (node (ref "U1") (pin "32") (pinfunction "PD2(INT0)_32") (pintype "bidirectional"))
      (node (ref "U6") (pin "4") (pinfunction "O_4") (pintype "output"))
    )
    (net (code "16") (name "/PUSH") (class "Default")
      (node (ref "R65") (pin "1") (pinfunction "1_1") (pintype "passive"))
      (node (ref "TP9") (pin "1") (pinfunction "1_1") (pintype "passive"))
      (node (ref "U6") (pin "5") (pinfunction "I_5") (pintype "input"))
    )
    (net (code "17") (name "/PUSH_FILT") (class "Default")
      (node (ref "U1") (pin "25") (pinfunction "PC2(ADC2)_25") (pintype "bidirectional"))
      (node (ref "U6") (pin "8") (pinfunction "O_8") (pintype "output"))
    )
    (net (code "18") (name "/RESET") (class "Default")
      (node (ref "C33") (pin "1") (pinfunction "1_1") (pintype "passive"))
      (node (ref "J3") (pin "5") (pinfunction "5_5") (pintype "passive"))
      (node (ref "R77") (pin "1") (pinfunction "1_1") (pintype "passive"))
      (node (ref "U1") (pin "29") (pinfunction "PC6(/RESET)_29") (pintype "bidirectional"))
    )
    (net (code "19") (name "/ROTA") (class "Default")
      (node (ref "C23") (pin "2") (pinfunction "2_2") (pintype "passive"))
      (node (ref "R53") (pin "1") (pinfunction "1_1") (pintype "passive"))
      (node (ref "S1") (pin "A") (pinfunction "A_A") (pintype "bidirectional"))
      (node (ref "U3") (pin "5") (pinfunction "I_5") (pintype "input"))
    )
    (net (code "20") (name "/ROTA_FILT") (class "Default")
      (node (ref "U1") (pin "2") (pinfunction "PD4(XCK/T0)_2") (pintype "bidirectional"))
      (node (ref "U3") (pin "4") (pinfunction "O_4") (pintype "output"))
    )
    (net (code "21") (name "/ROTB") (class "Default")
      (node (ref "C22") (pin "2") (pinfunction "2_2") (pintype "passive"))
      (node (ref "R52") (pin "1") (pinfunction "1_1") (pintype "passive"))
      (node (ref "S1") (pin "B") (pinfunction "B_B") (pintype "bidirectional"))
      (node (ref "U3") (pin "11") (pinfunction "I_11") (pintype "input"))
    )
    (net (code "22") (name "/ROTB_FILT") (class "Default")
      (node (ref "U1") (pin "1") (pinfunction "PD3(INT1)_1") (pintype "bidirectional"))
      (node (ref "U3") (pin "8") (pinfunction "O_8") (pintype "output"))
    )
    (net (code "23") (name "/ROTPUSH") (class "Default")
      (node (ref "C24") (pin "2") (pinfunction "2_2") (pintype "passive"))
      (node (ref "R54") (pin "1") (pinfunction "1_1") (pintype "passive"))
      (node (ref "S1") (pin "SW+") (pinfunction "SW+_SW+") (pintype "bidirectional"))
      (node (ref "U3") (pin "1") (pinfunction "I_1") (pintype "input"))
    )
    (net (code "24") (name "/RPUSH_FILT") (class "Default")
      (node (ref "U1") (pin "26") (pinfunction "PC3(ADC3)_26") (pintype "bidirectional"))
      (node (ref "U3") (pin "12") (pinfunction "O_12") (pintype "output"))
    )
    (net (code "25") (name "/RST") (class "Default")
      (node (ref "J6") (pin "5") (pinfunction "RST_5") (pintype "bidirectional"))
      (node (ref "R21") (pin "2") (pinfunction "2_2") (pintype "passive"))
    )
    (net (code "26") (name "/RX-I") (class "Default")
      (node (ref "J4") (pin "P$3") (pinfunction "RXI_P$3") (pintype "bidirectional"))
      (node (ref "U1") (pin "30") (pinfunction "PD0(RXD)_30") (pintype "bidirectional"))
    )
    (net (code "27") (name "/SCK") (class "Default")
      (node (ref "J3") (pin "3") (pinfunction "3_3") (pintype "passive"))
      (node (ref "R14") (pin "1") (pinfunction "1_1") (pintype "passive"))
      (node (ref "U1") (pin "17") (pinfunction "PB5(SCK)_17") (pintype "bidirectional"))
    )
    (net (code "28") (name "/SCL") (class "Default")
      (node (ref "L5") (pin "2") (pinfunction "2_2") (pintype "passive"))
      (node (ref "R57") (pin "1") (pinfunction "1_1") (pintype "passive"))
      (node (ref "TP7") (pin "1") (pinfunction "1_1") (pintype "passive"))
      (node (ref "U1") (pin "28") (pinfunction "PC5(ADC5/SCL)_28") (pintype "bidirectional"))
    )
    (net (code "29") (name "/SDA") (class "Default")
      (node (ref "L6") (pin "2") (pinfunction "2_2") (pintype "passive"))
      (node (ref "R58") (pin "1") (pinfunction "1_1") (pintype "passive"))
      (node (ref "TP6") (pin "1") (pinfunction "1_1") (pintype "passive"))
      (node (ref "U1") (pin "27") (pinfunction "PC4(ADC4/SDA)_27") (pintype "bidirectional"))
    )
    (net (code "30") (name "/SPARE") (class "Default")
      (node (ref "C9") (pin "1") (pinfunction "1_1") (pintype "passive"))
      (node (ref "R18") (pin "2") (pinfunction "2_2") (pintype "passive"))
      (node (ref "R99") (pin "2") (pinfunction "2_2") (pintype "passive"))
      (node (ref "U1") (pin "23") (pinfunction "PC0(ADC0)_23") (pintype "bidirectional"))
      (node (ref "U6") (pin "1") (pinfunction "I_1") (pintype "input"))
    )
    (net (code "31") (name "/SS") (class "Default")
      (node (ref "R29") (pin "1") (pinfunction "1_1") (pintype "passive"))
      (node (ref "U1") (pin "14") (pinfunction "PB2(SS/OC1B)_14") (pintype "bidirectional"))
    )
    (net (code "32") (name "/TEST") (class "Default")
      (node (ref "Q1") (pin "1") (pinfunction "G_1") (pintype "passive"))
      (node (ref "R27") (pin "2") (pinfunction "2_2") (pintype "passive"))
      (node (ref "R34") (pin "2") (pinfunction "2_2") (pintype "passive"))
      (node (ref "TP13") (pin "1") (pinfunction "1_1") (pintype "passive"))
    )
    (net (code "33") (name "/TX-O") (class "Default")
      (node (ref "J4") (pin "P$2") (pinfunction "TXO_P$2") (pintype "bidirectional"))
      (node (ref "U1") (pin "31") (pinfunction "PD1(TXD)_31") (pintype "bidirectional"))
    )
    (net (code "34") (name "/VOSEN") (class "Default")
      (node (ref "C13") (pin "2") (pinfunction "2_2") (pintype "passive"))
      (node (ref "D2") (pin "3") (pinfunction "AC_3") (pintype "passive"))
      (node (ref "R36") (pin "1") (pinfunction "1_1") (pintype "passive"))
      (node (ref "R37") (pin "2") (pinfunction "2_2") (pintype "passive"))
      (node (ref "TP3") (pin "1") (pinfunction "1_1") (pintype "passive"))
      (node (ref "U1") (pin "19") (pinfunction "ADC6_19") (pintype "bidirectional"))
    )
    (net (code "35") (name "/VOUT") (class "Default")
      (node (ref "D8") (pin "C") (pinfunction "K_C") (pintype "bidirectional"))
      (node (ref "J2") (pin "1") (pinfunction "1_1") (pintype "passive"))
      (node (ref "K1") (pin "4") (pinfunction "S_4") (pintype "passive"))
      (node (ref "K1") (pin "6") (pinfunction "P_6") (pintype "passive"))
      (node (ref "K1") (pin "7") (pinfunction "O_7") (pintype "passive"))
      (node (ref "R1") (pin "2") (pinfunction "2_2") (pintype "passive"))
      (node (ref "R12") (pin "2") (pinfunction "2_2") (pintype "passive"))
      (node (ref "R37") (pin "1") (pinfunction "1_1") (pintype "passive"))
      (node (ref "TP11") (pin "1") (pinfunction "1_1") (pintype "passive"))
    )
    (net (code "36") (name "/VO_TPS") (class "Default")
      (node (ref "C19") (pin "2") (pinfunction "2_2") (pintype "passive"))
      (node (ref "C34") (pin "2") (pinfunction "2_2") (pintype "passive"))
      (node (ref "C39") (pin "1") (pinfunction "1_1") (pintype "passive"))
      (node (ref "C40") (pin "1") (pinfunction "1_1") (pintype "passive"))
      (node (ref "C41") (pin "1") (pinfunction "1_1") (pintype "passive"))
      (node (ref "C42") (pin "1") (pinfunction "1_1") (pintype "passive"))
      (node (ref "C43") (pin "1") (pinfunction "1_1") (pintype "passive"))
      (node (ref "L2") (pin "2") (pinfunction "2_2") (pintype "passive"))
      (node (ref "R11") (pin "2") (pinfunction "2_2") (pintype "passive"))
      (node (ref "R12") (pin "1") (pinfunction "1_1") (pintype "passive"))
      (node (ref "TP14") (pin "1") (pinfunction "1_1") (pintype "passive"))
      (node (ref "U4") (pin "5") (pinfunction "RS+_5") (pintype "power_in"))
    )
    (net (code "37") (name "/VRELAY") (class "Default")
      (node (ref "D3") (pin "3") (pinfunction "AC_3") (pintype "passive"))
      (node (ref "K1") (pin "8") (pinfunction "-_8") (pintype "passive"))
      (node (ref "Q3") (pin "3") (pinfunction "D_3") (pintype "passive"))
      (node (ref "TP8") (pin "1") (pinfunction "1_1") (pintype "passive"))
    )
    (net (code "38") (name "5VMCU") (class "Default")
      (node (ref "C1") (pin "2") (pinfunction "2_2") (pintype "passive"))
      (node (ref "C12") (pin "2") (pinfunction "2_2") (pintype "passive"))
      (node (ref "C15") (pin "2") (pinfunction "2_2") (pintype "passive"))
      (node (ref "C2") (pin "2") (pinfunction "2_2") (pintype "passive"))
      (node (ref "C20") (pin "2") (pinfunction "2_2") (pintype "passive"))
      (node (ref "C25") (pin "2") (pinfunction "2_2") (pintype "passive"))
      (node (ref "C26") (pin "1") (pinfunction "1_1") (pintype "passive"))
      (node (ref "C31") (pin "2") (pinfunction "2_2") (pintype "passive"))
      (node (ref "C4") (pin "1") (pinfunction "1_1") (pintype "passive"))
      (node (ref "C44") (pin "2") (pinfunction "2_2") (pintype "passive"))
      (node (ref "C45") (pin "2") (pinfunction "2_2") (pintype "passive"))
      (node (ref "C46") (pin "2") (pinfunction "2_2") (pintype "passive"))
      (node (ref "C5") (pin "2") (pinfunction "2_2") (pintype "passive"))
      (node (ref "C50") (pin "2") (pinfunction "2_2") (pintype "passive"))
      (node (ref "C51") (pin "2") (pinfunction "2_2") (pintype "passive"))
      (node (ref "C52") (pin "1") (pinfunction "1_1") (pintype "passive"))
      (node (ref "C53") (pin "2") (pinfunction "2_2") (pintype "passive"))
      (node (ref "D2") (pin "2") (pinfunction "C_2") (pintype "passive"))
      (node (ref "D3") (pin "2") (pinfunction "C_2") (pintype "passive"))
      (node (ref "J3") (pin "2") (pinfunction "2_2") (pintype "passive"))
      (node (ref "J4") (pin "P$4") (pinfunction "VCC_P$4") (pintype "bidirectional"))
      (node (ref "J6") (pin "2") (pinfunction "VCC_2") (pintype "bidirectional"))
      (node (ref "K1") (pin "1") (pinfunction "+_1") (pintype "passive"))
      (node (ref "L1") (pin "2") (pinfunction "2_2") (pintype "passive"))
      (node (ref "R13") (pin "2") (pinfunction "2_2") (pintype "passive"))
      (node (ref "R15") (pin "1") (pinfunction "1_1") (pintype "passive"))
      (node (ref "R19") (pin "2") (pinfunction "2_2") (pintype "passive"))
      (node (ref "R35") (pin "1") (pinfunction "1_1") (pintype "passive"))
      (node (ref "R38") (pin "1") (pinfunction "1_1") (pintype "passive"))
      (node (ref "R40") (pin "1") (pinfunction "1_1") (pintype "passive"))
      (node (ref "R52") (pin "2") (pinfunction "2_2") (pintype "passive"))
      (node (ref "R53") (pin "2") (pinfunction "2_2") (pintype "passive"))
      (node (ref "R54") (pin "2") (pinfunction "2_2") (pintype "passive"))
      (node (ref "R57") (pin "2") (pinfunction "2_2") (pintype "passive"))
      (node (ref "R58") (pin "2") (pinfunction "2_2") (pintype "passive"))
      (node (ref "R66") (pin "1") (pinfunction "1_1") (pintype "passive"))
      (node (ref "R77") (pin "2") (pinfunction "2_2") (pintype "passive"))
      (node (ref "U1") (pin "18") (pinfunction "AVCC_18") (pintype "bidirectional"))
      (node (ref "U1") (pin "4") (pinfunction "VCC_4") (pintype "bidirectional"))
      (node (ref "U1") (pin "6") (pinfunction "VCC_6") (pintype "bidirectional"))
      (node (ref "U3") (pin "14") (pinfunction "VCC_14") (pintype "power_in"))
      (node (ref "U6") (pin "14") (pinfunction "VCC_14") (pintype "power_in"))
      (node (ref "U7") (pin "1") (pinfunction "VCC_1") (pintype "bidirectional"))
    )
    (net (code "39") (name "GND") (class "Default")
      (node (ref "C1") (pin "1") (pinfunction "1_1") (pintype "passive"))
      (node (ref "C10") (pin "1") (pinfunction "1_1") (pintype "passive"))
      (node (ref "C11") (pin "1") (pinfunction "1_1") (pintype "passive"))
      (node (ref "C12") (pin "1") (pinfunction "1_1") (pintype "passive"))
      (node (ref "C13") (pin "1") (pinfunction "1_1") (pintype "passive"))
      (node (ref "C14") (pin "1") (pinfunction "1_1") (pintype "passive"))
      (node (ref "C15") (pin "1") (pinfunction "1_1") (pintype "passive"))
      (node (ref "C16") (pin "1") (pinfunction "1_1") (pintype "passive"))
      (node (ref "C17") (pin "2") (pinfunction "2_2") (pintype "passive"))
      (node (ref "C18") (pin "2") (pinfunction "2_2") (pintype "passive"))
      (node (ref "C2") (pin "1") (pinfunction "1_1") (pintype "passive"))
      (node (ref "C20") (pin "1") (pinfunction "1_1") (pintype "passive"))
      (node (ref "C21") (pin "2") (pinfunction "2_2") (pintype "passive"))
      (node (ref "C22") (pin "1") (pinfunction "1_1") (pintype "passive"))
      (node (ref "C23") (pin "1") (pinfunction "1_1") (pintype "passive"))
      (node (ref "C24") (pin "1") (pinfunction "1_1") (pintype "passive"))
      (node (ref "C25") (pin "1") (pinfunction "1_1") (pintype "passive"))
      (node (ref "C26") (pin "2") (pinfunction "2_2") (pintype "passive"))
      (node (ref "C27") (pin "1") (pinfunction "1_1") (pintype "passive"))
      (node (ref "C28") (pin "1") (pinfunction "1_1") (pintype "passive"))
      (node (ref "C30") (pin "1") (pinfunction "1_1") (pintype "passive"))
      (node (ref "C31") (pin "1") (pinfunction "1_1") (pintype "passive"))
      (node (ref "C32") (pin "1") (pinfunction "1_1") (pintype "passive"))
      (node (ref "C34") (pin "1") (pinfunction "1_1") (pintype "passive"))
      (node (ref "C35") (pin "2") (pinfunction "2_2") (pintype "passive"))
      (node (ref "C36") (pin "1") (pinfunction "1_1") (pintype "passive"))
      (node (ref "C38") (pin "1") (pinfunction "1_1") (pintype "passive"))
      (node (ref "C39") (pin "2") (pinfunction "2_2") (pintype "passive"))
      (node (ref "C4") (pin "2") (pinfunction "2_2") (pintype "passive"))
      (node (ref "C40") (pin "2") (pinfunction "2_2") (pintype "passive"))
      (node (ref "C41") (pin "2") (pinfunction "2_2") (pintype "passive"))
      (node (ref "C42") (pin "2") (pinfunction "2_2") (pintype "passive"))
      (node (ref "C44") (pin "1") (pinfunction "1_1") (pintype "passive"))
      (node (ref "C45") (pin "1") (pinfunction "1_1") (pintype "passive"))
      (node (ref "C46") (pin "1") (pinfunction "1_1") (pintype "passive"))
      (node (ref "C47") (pin "1") (pinfunction "1_1") (pintype "passive"))
      (node (ref "C48") (pin "1") (pinfunction "1_1") (pintype "passive"))
      (node (ref "C49") (pin "1") (pinfunction "1_1") (pintype "passive"))
      (node (ref "C50") (pin "1") (pinfunction "1_1") (pintype "passive"))
      (node (ref "C51") (pin "1") (pinfunction "1_1") (pintype "passive"))
      (node (ref "C52") (pin "2") (pinfunction "2_2") (pintype "passive"))
      (node (ref "C53") (pin "1") (pinfunction "1_1") (pintype "passive"))
      (node (ref "C54") (pin "1") (pinfunction "1_1") (pintype "passive"))
      (node (ref "C6") (pin "2") (pinfunction "2_2") (pintype "passive"))
      (node (ref "C7") (pin "1") (pinfunction "1_1") (pintype "passive"))
      (node (ref "C8") (pin "1") (pinfunction "1_1") (pintype "passive"))
      (node (ref "C9") (pin "2") (pinfunction "2_2") (pintype "passive"))
      (node (ref "D1") (pin "+") (pinfunction "A_+") (pintype "bidirectional"))
      (node (ref "D2") (pin "1") (pinfunction "A_1") (pintype "passive"))
      (node (ref "D6") (pin "1") (pinfunction "A_1") (pintype "bidirectional"))
      (node (ref "D8") (pin "A") (pinfunction "A_A") (pintype "bidirectional"))
      (node (ref "J1") (pin "1") (pinfunction "1_1") (pintype "passive"))
      (node (ref "J2") (pin "2") (pinfunction "2_2") (pintype "passive"))
      (node (ref "J3") (pin "6") (pinfunction "6_6") (pintype "passive"))
      (node (ref "J4") (pin "P$5") (pinfunction "CTS_P$5") (pintype "bidirectional"))
      (node (ref "J4") (pin "P$6") (pinfunction "GND_P$6") (pintype "bidirectional"))
      (node (ref "J6") (pin "1") (pinfunction "GND_1") (pintype "bidirectional"))
      (node (ref "K1") (pin "2") (pinfunction "O_2") (pintype "passive"))
      (node (ref "K1") (pin "3") (pinfunction "P_3") (pintype "passive"))
      (node (ref "K1") (pin "5") (pinfunction "S_5") (pintype "passive"))
      (node (ref "OP1") (pin "3") (pinfunction "EMIT_3") (pintype "passive"))
      (node (ref "Q1") (pin "2") (pinfunction "S_2") (pintype "passive"))
      (node (ref "Q2") (pin "2") (pinfunction "S_2") (pintype "passive"))
      (node (ref "Q3") (pin "2") (pinfunction "S_2") (pintype "passive"))
      (node (ref "Q9") (pin "2") (pinfunction "S_2") (pintype "passive"))
      (node (ref "R16") (pin "2") (pinfunction "2_2") (pintype "passive"))
      (node (ref "R18") (pin "1") (pinfunction "1_1") (pintype "passive"))
      (node (ref "R22") (pin "2") (pinfunction "2_2") (pintype "passive"))
      (node (ref "R32") (pin "2") (pinfunction "2_2") (pintype "passive"))
      (node (ref "R34") (pin "1") (pinfunction "1_1") (pintype "passive"))
      (node (ref "R36") (pin "2") (pinfunction "2_2") (pintype "passive"))
      (node (ref "R43") (pin "1") (pinfunction "1_1") (pintype "passive"))
      (node (ref "R44") (pin "1") (pinfunction "1_1") (pintype "passive"))
      (node (ref "S1") (pin "C") (pinfunction "C_C") (pintype "bidirectional"))
      (node (ref "S1") (pin "SW-") (pinfunction "SW-_SW-") (pintype "bidirectional"))
      (node (ref "S2") (pin "2") (pinfunction "2_2") (pintype "passive"))
      (node (ref "TP1") (pin "1") (pinfunction "1_1") (pintype "passive"))
      (node (ref "TP12") (pin "1") (pinfunction "1_1") (pintype "passive"))
      (node (ref "U1") (pin "21") (pinfunction "GND_21") (pintype "bidirectional"))
      (node (ref "U1") (pin "3") (pinfunction "GND_3") (pintype "bidirectional"))
      (node (ref "U1") (pin "5") (pinfunction "AGND_5") (pintype "bidirectional"))
      (node (ref "U2") (pin "2") (pinfunction "GND_2") (pintype "bidirectional"))
      (node (ref "U3") (pin "7") (pinfunction "GND_7") (pintype "power_in"))
      (node (ref "U4") (pin "1") (pinfunction "GND_1") (pintype "passive"))
      (node (ref "U4") (pin "2") (pinfunction "GND_2_2") (pintype "passive"))
      (node (ref "U5") (pin "3") (pinfunction "GND_3") (pintype "bidirectional"))
      (node (ref "U6") (pin "7") (pinfunction "GND_7") (pintype "power_in"))
      (node (ref "U7") (pin "10") (pinfunction "A1_10") (pintype "bidirectional"))
      (node (ref "U7") (pin "16") (pinfunction "GND_16") (pintype "bidirectional"))
      (node (ref "U7") (pin "7") (pinfunction "A2_7") (pintype "bidirectional"))
      (node (ref "U7") (pin "8") (pinfunction "~{G}_8") (pintype "bidirectional"))
      (node (ref "U7") (pin "9") (pinfunction "A0_9") (pintype "bidirectional"))
      (node (ref "U8") (pin "7") (pinfunction "GND_7") (pintype "bidirectional"))
      (node (ref "U8") (pin "PAD") (pinfunction "PAD_PAD") (pintype "bidirectional"))
      (node (ref "X1") (pin "2") (pinfunction "2_2") (pintype "passive"))
    )
    (net (code "40") (name "Net-(BZ1-+)") (class "Default")
      (node (ref "BZ1") (pin "1") (pinfunction "+_1") (pintype "passive"))
      (node (ref "C27") (pin "2") (pinfunction "2_2") (pintype "passive"))
      (node (ref "L7") (pin "2") (pinfunction "2_2") (pintype "passive"))
      (node (ref "R61") (pin "2") (pinfunction "2_2") (pintype "passive"))
    )
    (net (code "41") (name "Net-(BZ1--)") (class "Default")
      (node (ref "BZ1") (pin "2") (pinfunction "-_2") (pintype "passive"))
      (node (ref "Q9") (pin "3") (pinfunction "D_3") (pintype "passive"))
      (node (ref "R61") (pin "1") (pinfunction "1_1") (pintype "passive"))
    )
    (net (code "42") (name "Net-(C10-Pad2)") (class "Default")
      (node (ref "C10") (pin "2") (pinfunction "2_2") (pintype "passive"))
      (node (ref "R13") (pin "1") (pinfunction "1_1") (pintype "passive"))
      (node (ref "R65") (pin "2") (pinfunction "2_2") (pintype "passive"))
      (node (ref "S2") (pin "4") (pinfunction "4_4") (pintype "passive"))
    )
    (net (code "43") (name "Net-(C36-Pad2)") (class "Default")
      (node (ref "C36") (pin "2") (pinfunction "2_2") (pintype "passive"))
      (node (ref "J1") (pin "2") (pinfunction "2_2") (pintype "passive"))
      (node (ref "PTC1") (pin "2") (pinfunction "2_2") (pintype "passive"))
    )
    (net (code "44") (name "Net-(C37-Pad1)") (class "Default")
      (node (ref "C37") (pin "1") (pinfunction "1_1") (pintype "passive"))
      (node (ref "R44") (pin "2") (pinfunction "2_2") (pintype "passive"))
    )
    (net (code "45") (name "Net-(D1-K)") (class "Default")
      (node (ref "C3") (pin "2") (pinfunction "2_2") (pintype "passive"))
      (node (ref "D1") (pin "-") (pinfunction "K_-") (pintype "bidirectional"))
      (node (ref "L1") (pin "1") (pinfunction "1_1") (pintype "passive"))
      (node (ref "U2") (pin "6") (pinfunction "LX_6") (pintype "bidirectional"))
    )
    (net (code "46") (name "Net-(D5-A)") (class "Default")
      (node (ref "D5") (pin "1") (pinfunction "A_1") (pintype "bidirectional"))
      (node (ref "PTC1") (pin "1") (pinfunction "1_1") (pintype "passive"))
    )
    (net (code "47") (name "Net-(D6-K)") (class "Default")
      (node (ref "C29") (pin "2") (pinfunction "2_2") (pintype "passive"))
      (node (ref "D6") (pin "2") (pinfunction "K_2") (pintype "bidirectional"))
      (node (ref "L2") (pin "1") (pinfunction "1_1") (pintype "passive"))
      (node (ref "U8") (pin "8") (pinfunction "PH_8") (pintype "bidirectional"))
    )
    (net (code "48") (name "Net-(J5-Pad1)") (class "Default")
      (node (ref "J5") (pin "1") (pinfunction "1_1") (pintype "passive"))
      (node (ref "L3") (pin "1") (pinfunction "1_1") (pintype "passive"))
    )
    (net (code "49") (name "Net-(J5-Pad2)") (class "Default")
      (node (ref "J5") (pin "2") (pinfunction "2_2") (pintype "passive"))
      (node (ref "L4") (pin "1") (pinfunction "1_1") (pintype "passive"))
    )
    (net (code "50") (name "Net-(J6-DC)") (class "Default")
      (node (ref "J6") (pin "6") (pinfunction "DC_6") (pintype "bidirectional"))
      (node (ref "R24") (pin "2") (pinfunction "2_2") (pintype "passive"))
    )
    (net (code "51") (name "Net-(L3-Pad2)") (class "Default")
      (node (ref "L3") (pin "2") (pinfunction "2_2") (pintype "passive"))
      (node (ref "R26") (pin "1") (pinfunction "1_1") (pintype "passive"))
    )
    (net (code "52") (name "Net-(L4-Pad2)") (class "Default")
      (node (ref "L4") (pin "2") (pinfunction "2_2") (pintype "passive"))
      (node (ref "R22") (pin "1") (pinfunction "1_1") (pintype "passive"))
    )
    (net (code "53") (name "Net-(LED1-C)") (class "Default")
      (node (ref "LED1") (pin "K") (pinfunction "C_K") (pintype "passive"))
      (node (ref "Q2") (pin "3") (pinfunction "D_3") (pintype "passive"))
    )
    (net (code "54") (name "Net-(LED1-PadA)") (class "Default")
      (node (ref "LED1") (pin "A") (pinfunction "A_A") (pintype "passive"))
      (node (ref "R35") (pin "2") (pinfunction "2_2") (pintype "passive"))
    )
    (net (code "55") (name "Net-(LED2-C)") (class "Default")
      (node (ref "LED2") (pin "K") (pinfunction "C_K") (pintype "passive"))
      (node (ref "LED3") (pin "K") (pinfunction "C_K") (pintype "passive"))
      (node (ref "Q1") (pin "3") (pinfunction "D_3") (pintype "passive"))
    )
    (net (code "56") (name "Net-(LED2-PadA)") (class "Default")
      (node (ref "LED2") (pin "A") (pinfunction "A_A") (pintype "passive"))
      (node (ref "R38") (pin "2") (pinfunction "2_2") (pintype "passive"))
    )
    (net (code "57") (name "Net-(LED3-PadA)") (class "Default")
      (node (ref "LED3") (pin "A") (pinfunction "A_A") (pintype "passive"))
      (node (ref "R40") (pin "2") (pinfunction "2_2") (pintype "passive"))
    )
    (net (code "58") (name "Net-(OP1-C)") (class "Default")
      (node (ref "OP1") (pin "2") (pinfunction "C_2") (pintype "passive"))
      (node (ref "R26") (pin "2") (pinfunction "2_2") (pintype "passive"))
    )
    (net (code "59") (name "Net-(Q2-G)") (class "Default")
      (node (ref "Q2") (pin "1") (pinfunction "G_1") (pintype "passive"))
      (node (ref "R31") (pin "2") (pinfunction "2_2") (pintype "passive"))
    )
    (net (code "60") (name "Net-(Q3-G)") (class "Default")
      (node (ref "Q3") (pin "1") (pinfunction "G_1") (pintype "passive"))
      (node (ref "R30") (pin "2") (pinfunction "2_2") (pintype "passive"))
    )
    (net (code "61") (name "Net-(Q9-G)") (class "Default")
      (node (ref "Q9") (pin "1") (pinfunction "G_1") (pintype "passive"))
      (node (ref "R28") (pin "2") (pinfunction "2_2") (pintype "passive"))
      (node (ref "R32") (pin "1") (pinfunction "1_1") (pintype "passive"))
    )
    (net (code "62") (name "Net-(U1-PB1(OC1A))") (class "Default")
      (node (ref "R27") (pin "1") (pinfunction "1_1") (pintype "passive"))
      (node (ref "U1") (pin "13") (pinfunction "PB1(OC1A)_13") (pintype "bidirectional"))
    )
    (net (code "63") (name "Net-(U1-PB6(XTAL1{slash}TOSC1))") (class "Default")
      (node (ref "U1") (pin "7") (pinfunction "PB6(XTAL1/TOSC1)_7") (pintype "bidirectional"))
      (node (ref "X1") (pin "3") (pinfunction "3_3") (pintype "passive"))
    )
    (net (code "64") (name "Net-(U1-PB7(XTAL2{slash}TOSC2))") (class "Default")
      (node (ref "U1") (pin "8") (pinfunction "PB7(XTAL2/TOSC2)_8") (pintype "bidirectional"))
      (node (ref "X1") (pin "1") (pinfunction "1_1") (pintype "passive"))
    )
    (net (code "65") (name "Net-(U2-BST)") (class "Default")
      (node (ref "C3") (pin "1") (pinfunction "1_1") (pintype "passive"))
      (node (ref "U2") (pin "1") (pinfunction "BST_1") (pintype "bidirectional"))
    )
    (net (code "66") (name "Net-(U2-FB)") (class "Default")
      (node (ref "C5") (pin "1") (pinfunction "1_1") (pintype "passive"))
      (node (ref "R15") (pin "2") (pinfunction "2_2") (pintype "passive"))
      (node (ref "R16") (pin "1") (pinfunction "1_1") (pintype "passive"))
      (node (ref "U2") (pin "3") (pinfunction "FB_3") (pintype "bidirectional"))
    )
    (net (code "67") (name "Net-(U3A-I)") (class "Default")
      (node (ref "C49") (pin "2") (pinfunction "2_2") (pintype "passive"))
      (node (ref "R25") (pin "2") (pinfunction "2_2") (pintype "passive"))
      (node (ref "U3") (pin "13") (pinfunction "I_13") (pintype "input"))
    )
    (net (code "68") (name "Net-(U3B-O)") (class "Default")
      (node (ref "R2") (pin "1") (pinfunction "1_1") (pintype "passive"))
      (node (ref "U3") (pin "10") (pinfunction "O_10") (pintype "output"))
    )
    (net (code "69") (name "Net-(U3C-I)") (class "Default")
      (node (ref "C47") (pin "2") (pinfunction "2_2") (pintype "passive"))
      (node (ref "R2") (pin "2") (pinfunction "2_2") (pintype "passive"))
      (node (ref "U3") (pin "9") (pinfunction "I_9") (pintype "input"))
    )
    (net (code "70") (name "Net-(U3D-O)") (class "Default")
      (node (ref "R25") (pin "1") (pinfunction "1_1") (pintype "passive"))
      (node (ref "U3") (pin "2") (pinfunction "O_2") (pintype "output"))
    )
    (net (code "71") (name "Net-(U3E-I)") (class "Default")
      (node (ref "C48") (pin "2") (pinfunction "2_2") (pintype "passive"))
      (node (ref "R20") (pin "2") (pinfunction "2_2") (pintype "passive"))
      (node (ref "U3") (pin "3") (pinfunction "I_3") (pintype "input"))
    )
    (net (code "72") (name "Net-(U3F-O)") (class "Default")
      (node (ref "R20") (pin "1") (pinfunction "1_1") (pintype "passive"))
      (node (ref "U3") (pin "6") (pinfunction "O_6") (pintype "output"))
    )
    (net (code "73") (name "Net-(U4-RS-)") (class "Default")
      (node (ref "C43") (pin "2") (pinfunction "2_2") (pintype "passive"))
      (node (ref "R1") (pin "1") (pinfunction "1_1") (pintype "passive"))
      (node (ref "U4") (pin "4") (pinfunction "RS-_4") (pintype "input"))
    )
    (net (code "74") (name "Net-(U6A-O)") (class "Default")
      (node (ref "R39") (pin "1") (pinfunction "1_1") (pintype "passive"))
      (node (ref "U6") (pin "12") (pinfunction "O_12") (pintype "output"))
    )
    (net (code "75") (name "Net-(U6B-I)") (class "Default")
      (node (ref "C54") (pin "2") (pinfunction "2_2") (pintype "passive"))
      (node (ref "R39") (pin "2") (pinfunction "2_2") (pintype "passive"))
      (node (ref "U6") (pin "11") (pinfunction "I_11") (pintype "input"))
    )
    (net (code "76") (name "Net-(U6C-I)") (class "Default")
      (node (ref "C14") (pin "2") (pinfunction "2_2") (pintype "passive"))
      (node (ref "R33") (pin "2") (pinfunction "2_2") (pintype "passive"))
      (node (ref "U6") (pin "9") (pinfunction "I_9") (pintype "input"))
    )
    (net (code "77") (name "Net-(U6D-O)") (class "Default")
      (node (ref "R23") (pin "1") (pinfunction "1_1") (pintype "passive"))
      (node (ref "U6") (pin "2") (pinfunction "O_2") (pintype "output"))
    )
    (net (code "78") (name "Net-(U6E-I)") (class "Default")
      (node (ref "C11") (pin "2") (pinfunction "2_2") (pintype "passive"))
      (node (ref "R23") (pin "2") (pinfunction "2_2") (pintype "passive"))
      (node (ref "U6") (pin "3") (pinfunction "I_3") (pintype "input"))
    )
    (net (code "79") (name "Net-(U6F-O)") (class "Default")
      (node (ref "R33") (pin "1") (pinfunction "1_1") (pintype "passive"))
      (node (ref "U6") (pin "6") (pinfunction "O_6") (pintype "output"))
    )
    (net (code "80") (name "Net-(U7-DRAIN0)") (class "Default")
      (node (ref "R6") (pin "1") (pinfunction "1_1") (pintype "passive"))
      (node (ref "U7") (pin "3") (pinfunction "DRAIN0_3") (pintype "bidirectional"))
    )
    (net (code "81") (name "Net-(U7-DRAIN1)") (class "Default")
      (node (ref "R5") (pin "1") (pinfunction "1_1") (pintype "passive"))
      (node (ref "U7") (pin "4") (pinfunction "DRAIN1_4") (pintype "bidirectional"))
    )
    (net (code "82") (name "Net-(U7-DRAIN2)") (class "Default")
      (node (ref "R4") (pin "1") (pinfunction "1_1") (pintype "passive"))
      (node (ref "U7") (pin "5") (pinfunction "DRAIN2_5") (pintype "bidirectional"))
    )
    (net (code "83") (name "Net-(U7-DRAIN3)") (class "Default")
      (node (ref "R3") (pin "1") (pinfunction "1_1") (pintype "passive"))
      (node (ref "U7") (pin "6") (pinfunction "DRAIN3_6") (pintype "bidirectional"))
    )
    (net (code "84") (name "Net-(U7-DRAIN4)") (class "Default")
      (node (ref "R10") (pin "1") (pinfunction "1_1") (pintype "passive"))
      (node (ref "U7") (pin "11") (pinfunction "DRAIN4_11") (pintype "bidirectional"))
    )
    (net (code "85") (name "Net-(U7-DRAIN5)") (class "Default")
      (node (ref "R9") (pin "1") (pinfunction "1_1") (pintype "passive"))
      (node (ref "U7") (pin "12") (pinfunction "DRAIN5_12") (pintype "bidirectional"))
    )
    (net (code "86") (name "Net-(U7-DRAIN6)") (class "Default")
      (node (ref "R8") (pin "1") (pinfunction "1_1") (pintype "passive"))
      (node (ref "U7") (pin "13") (pinfunction "DRAIN6_13") (pintype "bidirectional"))
    )
    (net (code "87") (name "Net-(U7-DRAIN7)") (class "Default")
      (node (ref "R7") (pin "1") (pinfunction "1_1") (pintype "passive"))
      (node (ref "U7") (pin "14") (pinfunction "DRAIN7_14") (pintype "bidirectional"))
    )
    (net (code "88") (name "Net-(U7-SCL)") (class "Default")
      (node (ref "L5") (pin "1") (pinfunction "1_1") (pintype "passive"))
      (node (ref "U7") (pin "15") (pinfunction "SCL_15") (pintype "bidirectional"))
    )
    (net (code "89") (name "Net-(U7-SDA)") (class "Default")
      (node (ref "L6") (pin "1") (pinfunction "1_1") (pintype "passive"))
      (node (ref "U7") (pin "2") (pinfunction "SDA_2") (pintype "bidirectional"))
    )
    (net (code "90") (name "Net-(U8-BOOT)") (class "Default")
      (node (ref "C29") (pin "1") (pinfunction "1_1") (pintype "passive"))
      (node (ref "U8") (pin "1") (pinfunction "BOOT_1") (pintype "bidirectional"))
    )
    (net (code "91") (name "Net-(U8-COMP)") (class "Default")
      (node (ref "C37") (pin "2") (pinfunction "2_2") (pintype "passive"))
      (node (ref "C38") (pin "2") (pinfunction "2_2") (pintype "passive"))
      (node (ref "U8") (pin "6") (pinfunction "COMP_6") (pintype "bidirectional"))
    )
    (net (code "92") (name "Net-(U8-SS)") (class "Default")
      (node (ref "C30") (pin "2") (pinfunction "2_2") (pintype "passive"))
      (node (ref "U8") (pin "4") (pinfunction "SS_4") (pintype "bidirectional"))
    )
    (net (code "93") (name "Net-(U8-VSENSE)") (class "Default")
      (node (ref "C19") (pin "1") (pinfunction "1_1") (pintype "passive"))
      (node (ref "R10") (pin "2") (pinfunction "2_2") (pintype "passive"))
      (node (ref "R11") (pin "1") (pinfunction "1_1") (pintype "passive"))
      (node (ref "R3") (pin "2") (pinfunction "2_2") (pintype "passive"))
      (node (ref "R4") (pin "2") (pinfunction "2_2") (pintype "passive"))
      (node (ref "R5") (pin "2") (pinfunction "2_2") (pintype "passive"))
      (node (ref "R6") (pin "2") (pinfunction "2_2") (pintype "passive"))
      (node (ref "R7") (pin "2") (pinfunction "2_2") (pintype "passive"))
      (node (ref "R8") (pin "2") (pinfunction "2_2") (pintype "passive"))
      (node (ref "R9") (pin "2") (pinfunction "2_2") (pintype "passive"))
      (node (ref "U8") (pin "5") (pinfunction "VSENSE_5") (pintype "bidirectional"))
    )
    (net (code "94") (name "VCC") (class "Default")
      (node (ref "C17") (pin "1") (pinfunction "1_1") (pintype "passive"))
      (node (ref "C18") (pin "1") (pinfunction "1_1") (pintype "passive"))
      (node (ref "C21") (pin "1") (pinfunction "1_1") (pintype "passive"))
      (node (ref "C28") (pin "2") (pinfunction "2_2") (pintype "passive"))
      (node (ref "C35") (pin "1") (pinfunction "1_1") (pintype "passive"))
      (node (ref "C6") (pin "1") (pinfunction "1_1") (pintype "passive"))
      (node (ref "C7") (pin "2") (pinfunction "2_2") (pintype "passive"))
      (node (ref "D5") (pin "2") (pinfunction "K_2") (pintype "bidirectional"))
      (node (ref "L7") (pin "1") (pinfunction "1_1") (pintype "passive"))
      (node (ref "U2") (pin "4") (pinfunction "EN_4") (pintype "bidirectional"))
      (node (ref "U2") (pin "5") (pinfunction "VCC_5") (pintype "bidirectional"))
      (node (ref "U5") (pin "2") (pinfunction "IN_2") (pintype "bidirectional"))
      (node (ref "U8") (pin "2") (pinfunction "VIN_2") (pintype "bidirectional"))
    )
    (net (code "95") (name "VCCIO") (class "Default")
      (node (ref "C16") (pin "2") (pinfunction "2_2") (pintype "passive"))
      (node (ref "C8") (pin "2") (pinfunction "2_2") (pintype "passive"))
      (node (ref "OP1") (pin "1") (pinfunction "A_1") (pintype "passive"))
      (node (ref "TP2") (pin "1") (pinfunction "1_1") (pintype "passive"))
      (node (ref "U5") (pin "1") (pinfunction "OUT_1") (pintype "bidirectional"))
    )
    (net (code "96") (name "unconnected-(D3-A-Pad1)") (class "Default")
      (node (ref "D3") (pin "1") (pinfunction "A_1") (pintype "passive"))
    )
    (net (code "97") (name "unconnected-(S2-Pad1)") (class "Default")
      (node (ref "S2") (pin "1") (pinfunction "1_1") (pintype "passive"))
    )
    (net (code "98") (name "unconnected-(S2-Pad3)") (class "Default")
      (node (ref "S2") (pin "3") (pinfunction "3_3") (pintype "passive"))
    )
  )
)
